# ham_ii_digital_interface.net
KiCad netlist of a schematic drawn in EAGLE
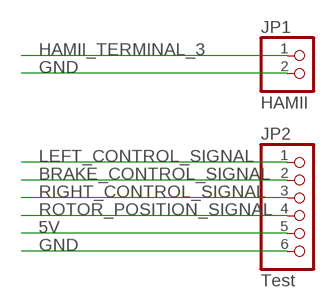
[diagram p0: schematic, sheet 1]
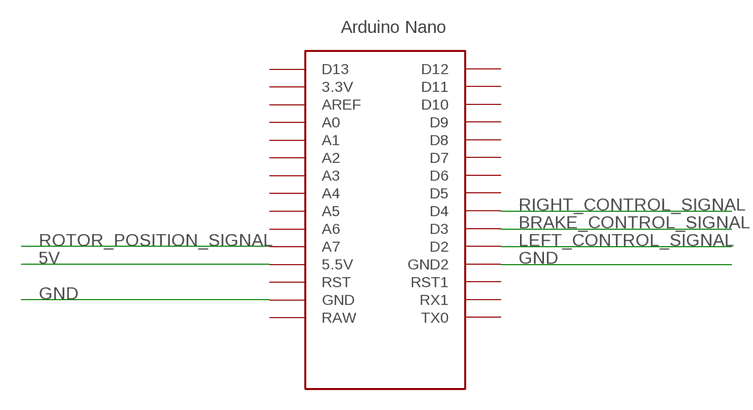
[diagram p1: schematic, sheet 2]
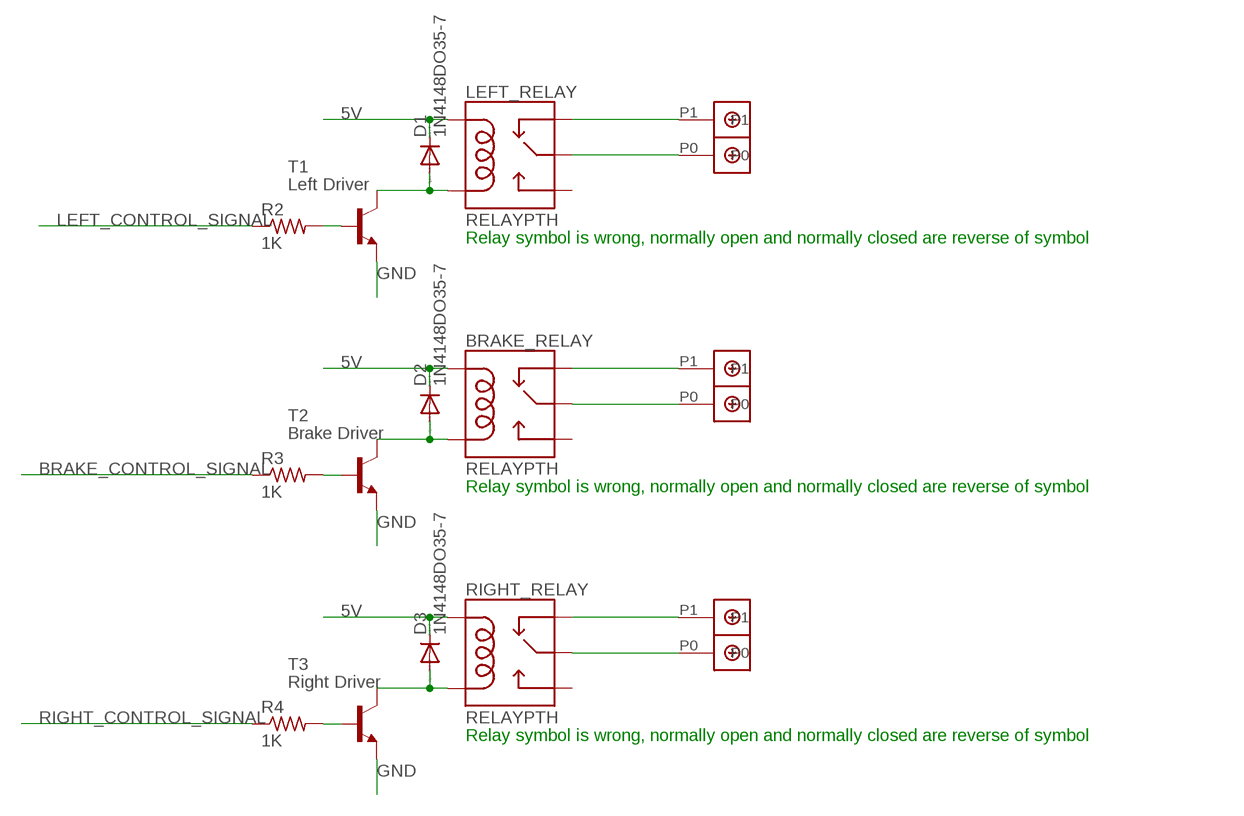
[diagram p2: schematic, sheet 3]
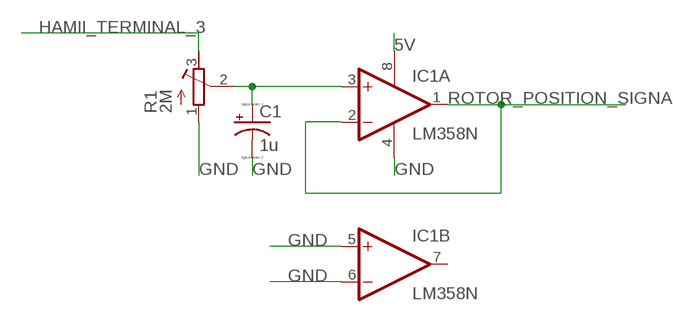
[diagram p3: schematic, sheet 4]

(export (version "E")
  (design (tool "Eeschema 10.0.6"))
  (components
    (comp (ref "C1")
      (value "1u")
      (footprint "eagle-import:E2-5")
      (libsource (lib "eagle-import") (part "CPOL-USE2-5"))
    )
    (comp (ref "IC1")
      (value "LM358N")
      (footprint "eagle-import:DIL08")
      (libsource (lib "eagle-import") (part "LM358N"))
    )
    (comp (ref "R1")
      (value "2M")
      (footprint "eagle-import:RTRIM3296W")
      (libsource (lib "eagle-import") (part "R-TRIMM3296W"))
    )
    (comp (ref "JP1")
      (value "HAMII")
      (footprint "eagle-import:1X02")
      (libsource (lib "eagle-import") (part "PINHD-1X2"))
    )
    (comp (ref "JP2")
      (value "Test")
      (footprint "eagle-import:1X06")
      (libsource (lib "eagle-import") (part "PINHD-1X6"))
    )
    (comp (ref "BRAKE_RELAY")
      (value "RELAYPTH")
      (footprint "eagle-import:SRD-05VDC-SL-C")
      (libsource (lib "eagle-import") (part "RELAYPTH"))
    )
    (comp (ref "D1")
      (value "1N4148DO35-7")
      (footprint "eagle-import:DO35-7")
      (libsource (lib "eagle-import") (part "1N4148DO35-7"))
    )
    (comp (ref "D2")
      (value "1N4148DO35-7")
      (footprint "eagle-import:DO35-7")
      (libsource (lib "eagle-import") (part "1N4148DO35-7"))
    )
    (comp (ref "D3")
      (value "1N4148DO35-7")
      (footprint "eagle-import:DO35-7")
      (libsource (lib "eagle-import") (part "1N4148DO35-7"))
    )
    (comp (ref "LEFT_RELAY")
      (value "RELAYPTH")
      (footprint "eagle-import:SRD-05VDC-SL-C")
      (libsource (lib "eagle-import") (part "RELAYPTH"))
    )
    (comp (ref "R2")
      (value "1K")
      (footprint "eagle-import:0207_10")
      (libsource (lib "eagle-import") (part "R-US_0207/10"))
    )
    (comp (ref "R3")
      (value "1K")
      (footprint "eagle-import:0207_10")
      (libsource (lib "eagle-import") (part "R-US_0207/10"))
    )
    (comp (ref "R4")
      (value "1K")
      (footprint "eagle-import:0207_10")
      (libsource (lib "eagle-import") (part "R-US_0207/10"))
    )
    (comp (ref "RIGHT_RELAY")
      (value "RELAYPTH")
      (footprint "eagle-import:SRD-05VDC-SL-C")
      (libsource (lib "eagle-import") (part "RELAYPTH"))
    )
    (comp (ref "T1")
      (value "Left Driver")
      (footprint "eagle-import:TO92")
      (libsource (lib "eagle-import") (part "-NPN-TO92"))
    )
    (comp (ref "T2")
      (value "Brake Driver")
      (footprint "eagle-import:TO92")
      (libsource (lib "eagle-import") (part "-NPN-TO92"))
    )
    (comp (ref "T3")
      (value "Right Driver")
      (footprint "eagle-import:TO92")
      (libsource (lib "eagle-import") (part "-NPN-TO92"))
    )
    (comp (ref "U$5")
      (value "DBCONN-1X2")
      (footprint "eagle-import:DBCONN-1X2")
      (libsource (lib "eagle-import") (part "DBCONN-1X2"))
    )
    (comp (ref "U$6")
      (value "DBCONN-1X2")
      (footprint "eagle-import:DBCONN-1X2")
      (libsource (lib "eagle-import") (part "DBCONN-1X2"))
    )
    (comp (ref "U$7")
      (value "DBCONN-1X2")
      (footprint "eagle-import:DBCONN-1X2")
      (libsource (lib "eagle-import") (part "DBCONN-1X2"))
    )
    (comp (ref "U$1")
      (value "NANO")
      (footprint "eagle-import:NANO")
      (libsource (lib "eagle-import") (part "NANO"))
    )
  )
  (nets
    (net (code "1") (name "5V") (class "Default")
      (node (ref "BRAKE_RELAY") (pin "COIL1") (pinfunction "COIL1_COIL1") (pintype "bidirectional"))
      (node (ref "D1") (pin "C") (pinfunction "C_C") (pintype "passive"))
      (node (ref "D2") (pin "C") (pinfunction "C_C") (pintype "passive"))
      (node (ref "D3") (pin "C") (pinfunction "C_C") (pintype "passive"))
      (node (ref "IC1") (pin "8") (pinfunction "V+_8") (pintype "power_in"))
      (node (ref "JP2") (pin "5") (pinfunction "5_5") (pintype "passive"))
      (node (ref "LEFT_RELAY") (pin "COIL1") (pinfunction "COIL1_COIL1") (pintype "bidirectional"))
      (node (ref "RIGHT_RELAY") (pin "COIL1") (pinfunction "COIL1_COIL1") (pintype "bidirectional"))
      (node (ref "U$1") (pin "5V") (pinfunction "5.5V_5V") (pintype "bidirectional"))
    )
    (net (code "2") (name "BRAKE_CONTROL_SIGNAL") (class "Default")
      (node (ref "JP2") (pin "2") (pinfunction "2_2") (pintype "passive"))
      (node (ref "R3") (pin "1") (pinfunction "1_1") (pintype "passive"))
      (node (ref "U$1") (pin "D3") (pinfunction "D3_D3") (pintype "bidirectional"))
    )
    (net (code "3") (name "GND") (class "Default")
      (node (ref "C1") (pin "-") (pinfunction "-_-") (pintype "passive"))
      (node (ref "IC1") (pin "4") (pinfunction "V-_4") (pintype "power_in"))
      (node (ref "IC1") (pin "5") (pinfunction "+IN_5") (pintype "input"))
      (node (ref "IC1") (pin "6") (pinfunction "-IN_6") (pintype "input"))
      (node (ref "JP1") (pin "2") (pinfunction "2_2") (pintype "passive"))
      (node (ref "JP2") (pin "6") (pinfunction "6_6") (pintype "passive"))
      (node (ref "R1") (pin "1") (pinfunction "A_1") (pintype "passive"))
      (node (ref "T1") (pin "1") (pinfunction "E_1") (pintype "passive"))
      (node (ref "T2") (pin "1") (pinfunction "E_1") (pintype "passive"))
      (node (ref "T3") (pin "1") (pinfunction "E_1") (pintype "passive"))
      (node (ref "U$1") (pin "GND") (pinfunction "GND_GND") (pintype "bidirectional"))
      (node (ref "U$1") (pin "GND1") (pinfunction "GND2_GND1") (pintype "bidirectional"))
    )
    (net (code "4") (name "HAMII_TERMINAL_3") (class "Default")
      (node (ref "JP1") (pin "1") (pinfunction "1_1") (pintype "passive"))
      (node (ref "R1") (pin "3") (pinfunction "E_3") (pintype "passive"))
    )
    (net (code "5") (name "LEFT_CONTROL_SIGNAL") (class "Default")
      (node (ref "JP2") (pin "1") (pinfunction "1_1") (pintype "passive"))
      (node (ref "R2") (pin "1") (pinfunction "1_1") (pintype "passive"))
      (node (ref "U$1") (pin "D2") (pinfunction "D2_D2") (pintype "bidirectional"))
    )
    (net (code "6") (name "Net-(BRAKE_RELAY-PadSWCOMMON)") (class "Default")
      (node (ref "BRAKE_RELAY") (pin "SWCOMMON") (pinfunction "SWCOMMON_SWCOMMON") (pintype "bidirectional"))
      (node (ref "U$6") (pin "P0") (pinfunction "P0_P0") (pintype "bidirectional"))
    )
    (net (code "7") (name "Net-(BRAKE_RELAY-SWCLOSE)") (class "Default")
      (node (ref "BRAKE_RELAY") (pin "SWCLOSED") (pinfunction "SWCLOSE_SWCLOSED") (pintype "bidirectional"))
      (node (ref "U$6") (pin "P1") (pinfunction "P1_P1") (pintype "bidirectional"))
    )
    (net (code "8") (name "Net-(IC1A-+IN)") (class "Default")
      (node (ref "C1") (pin "+") (pinfunction "+_+") (pintype "passive"))
      (node (ref "IC1") (pin "3") (pinfunction "+IN_3") (pintype "input"))
      (node (ref "R1") (pin "2") (pinfunction "S_2") (pintype "passive"))
    )
    (net (code "9") (name "Net-(LEFT_RELAY-PadSWCOMMON)") (class "Default")
      (node (ref "LEFT_RELAY") (pin "SWCOMMON") (pinfunction "SWCOMMON_SWCOMMON") (pintype "bidirectional"))
      (node (ref "U$5") (pin "P0") (pinfunction "P0_P0") (pintype "bidirectional"))
    )
    (net (code "10") (name "Net-(LEFT_RELAY-SWCLOSE)") (class "Default")
      (node (ref "LEFT_RELAY") (pin "SWCLOSED") (pinfunction "SWCLOSE_SWCLOSED") (pintype "bidirectional"))
      (node (ref "U$5") (pin "P1") (pinfunction "P1_P1") (pintype "bidirectional"))
    )
    (net (code "11") (name "Net-(RIGHT_RELAY-PadSWCOMMON)") (class "Default")
      (node (ref "RIGHT_RELAY") (pin "SWCOMMON") (pinfunction "SWCOMMON_SWCOMMON") (pintype "bidirectional"))
      (node (ref "U$7") (pin "P0") (pinfunction "P0_P0") (pintype "bidirectional"))
    )
    (net (code "12") (name "Net-(RIGHT_RELAY-SWCLOSE)") (class "Default")
      (node (ref "RIGHT_RELAY") (pin "SWCLOSED") (pinfunction "SWCLOSE_SWCLOSED") (pintype "bidirectional"))
      (node (ref "U$7") (pin "P1") (pinfunction "P1_P1") (pintype "bidirectional"))
    )
    (net (code "13") (name "Net-(T1-B)") (class "Default")
      (node (ref "R2") (pin "2") (pinfunction "2_2") (pintype "passive"))
      (node (ref "T1") (pin "2") (pinfunction "B_2") (pintype "passive"))
    )
    (net (code "14") (name "Net-(T1-C)") (class "Default")
      (node (ref "D1") (pin "A") (pinfunction "A_A") (pintype "passive"))
      (node (ref "LEFT_RELAY") (pin "COIL0") (pinfunction "COIL0_COIL0") (pintype "bidirectional"))
      (node (ref "T1") (pin "3") (pinfunction "C_3") (pintype "passive"))
    )
    (net (code "15") (name "Net-(T2-B)") (class "Default")
      (node (ref "R3") (pin "2") (pinfunction "2_2") (pintype "passive"))
      (node (ref "T2") (pin "2") (pinfunction "B_2") (pintype "passive"))
    )
    (net (code "16") (name "Net-(T2-C)") (class "Default")
      (node (ref "BRAKE_RELAY") (pin "COIL0") (pinfunction "COIL0_COIL0") (pintype "bidirectional"))
      (node (ref "D2") (pin "A") (pinfunction "A_A") (pintype "passive"))
      (node (ref "T2") (pin "3") (pinfunction "C_3") (pintype "passive"))
    )
    (net (code "17") (name "Net-(T3-B)") (class "Default")
      (node (ref "R4") (pin "2") (pinfunction "2_2") (pintype "passive"))
      (node (ref "T3") (pin "2") (pinfunction "B_2") (pintype "passive"))
    )
    (net (code "18") (name "Net-(T3-C)") (class "Default")
      (node (ref "D3") (pin "A") (pinfunction "A_A") (pintype "passive"))
      (node (ref "RIGHT_RELAY") (pin "COIL0") (pinfunction "COIL0_COIL0") (pintype "bidirectional"))
      (node (ref "T3") (pin "3") (pinfunction "C_3") (pintype "passive"))
    )
    (net (code "19") (name "RIGHT_CONTROL_SIGNAL") (class "Default")
      (node (ref "JP2") (pin "3") (pinfunction "3_3") (pintype "passive"))
      (node (ref "R4") (pin "1") (pinfunction "1_1") (pintype "passive"))
      (node (ref "U$1") (pin "D4") (pinfunction "D4_D4") (pintype "bidirectional"))
    )
    (net (code "20") (name "ROTOR_POSITION_SIGNAL") (class "Default")
      (node (ref "IC1") (pin "1") (pinfunction "OUT_1") (pintype "output"))
      (node (ref "IC1") (pin "2") (pinfunction "-IN_2") (pintype "input"))
      (node (ref "JP2") (pin "4") (pinfunction "4_4") (pintype "passive"))
      (node (ref "U$1") (pin "A7") (pinfunction "A7_A7") (pintype "bidirectional"))
    )
    (net (code "21") (name "unconnected-(BRAKE_RELAY-PadSWOPEN)") (class "Default")
      (node (ref "BRAKE_RELAY") (pin "SWOPEN") (pinfunction "SWOPEN_SWOPEN") (pintype "bidirectional"))
    )
    (net (code "22") (name "unconnected-(IC1B-OUT-Pad7)") (class "Default")
      (node (ref "IC1") (pin "7") (pinfunction "OUT_7") (pintype "output"))
    )
    (net (code "23") (name "unconnected-(LEFT_RELAY-PadSWOPEN)") (class "Default")
      (node (ref "LEFT_RELAY") (pin "SWOPEN") (pinfunction "SWOPEN_SWOPEN") (pintype "bidirectional"))
    )
    (net (code "24") (name "unconnected-(RIGHT_RELAY-PadSWOPEN)") (class "Default")
      (node (ref "RIGHT_RELAY") (pin "SWOPEN") (pinfunction "SWOPEN_SWOPEN") (pintype "bidirectional"))
    )
    (net (code "25") (name "unconnected-(U$1-Pad3.3V)") (class "Default")
      (node (ref "U$1") (pin "3.3V") (pinfunction "3.3V_3.3V") (pintype "bidirectional"))
    )
    (net (code "26") (name "unconnected-(U$1-PadA0)") (class "Default")
      (node (ref "U$1") (pin "A0") (pinfunction "A0_A0") (pintype "bidirectional"))
    )
    (net (code "27") (name "unconnected-(U$1-PadA1)") (class "Default")
      (node (ref "U$1") (pin "A1") (pinfunction "A1_A1") (pintype "bidirectional"))
    )
    (net (code "28") (name "unconnected-(U$1-PadA2)") (class "Default")
      (node (ref "U$1") (pin "A2") (pinfunction "A2_A2") (pintype "bidirectional"))
    )
    (net (code "29") (name "unconnected-(U$1-PadA3)") (class "Default")
      (node (ref "U$1") (pin "A3") (pinfunction "A3_A3") (pintype "bidirectional"))
    )
    (net (code "30") (name "unconnected-(U$1-PadA4)") (class "Default")
      (node (ref "U$1") (pin "A4") (pinfunction "A4_A4") (pintype "bidirectional"))
    )
    (net (code "31") (name "unconnected-(U$1-PadA5)") (class "Default")
      (node (ref "U$1") (pin "A5") (pinfunction "A5_A5") (pintype "bidirectional"))
    )
    (net (code "32") (name "unconnected-(U$1-PadA6)") (class "Default")
      (node (ref "U$1") (pin "A6") (pinfunction "A6_A6") (pintype "bidirectional"))
    )
    (net (code "33") (name "unconnected-(U$1-PadAREF)") (class "Default")
      (node (ref "U$1") (pin "AREF") (pinfunction "AREF_AREF") (pintype "bidirectional"))
    )
    (net (code "34") (name "unconnected-(U$1-PadD5)") (class "Default")
      (node (ref "U$1") (pin "D5") (pinfunction "D5_D5") (pintype "bidirectional"))
    )
    (net (code "35") (name "unconnected-(U$1-PadD6)") (class "Default")
      (node (ref "U$1") (pin "D6") (pinfunction "D6_D6") (pintype "bidirectional"))
    )
    (net (code "36") (name "unconnected-(U$1-PadD7)") (class "Default")
      (node (ref "U$1") (pin "D7") (pinfunction "D7_D7") (pintype "bidirectional"))
    )
    (net (code "37") (name "unconnected-(U$1-PadD8)") (class "Default")
      (node (ref "U$1") (pin "D8") (pinfunction "D8_D8") (pintype "bidirectional"))
    )
    (net (code "38") (name "unconnected-(U$1-PadD9)") (class "Default")
      (node (ref "U$1") (pin "D9") (pinfunction "D9_D9") (pintype "bidirectional"))
    )
    (net (code "39") (name "unconnected-(U$1-PadD10)") (class "Default")
      (node (ref "U$1") (pin "D10") (pinfunction "D10_D10") (pintype "bidirectional"))
    )
    (net (code "40") (name "unconnected-(U$1-PadD11)") (class "Default")
      (node (ref "U$1") (pin "D11") (pinfunction "D11_D11") (pintype "bidirectional"))
    )
    (net (code "41") (name "unconnected-(U$1-PadD12)") (class "Default")
      (node (ref "U$1") (pin "D12") (pinfunction "D12_D12") (pintype "bidirectional"))
    )
    (net (code "42") (name "unconnected-(U$1-PadD13)") (class "Default")
      (node (ref "U$1") (pin "D13") (pinfunction "D13_D13") (pintype "bidirectional"))
    )
    (net (code "43") (name "unconnected-(U$1-PadICSP1)") (class "Default")
      (node (ref "U$1") (pin "ICSP1") (pinfunction "ICSP1_ICSP1") (pintype "bidirectional"))
    )
    (net (code "44") (name "unconnected-(U$1-PadICSP2)") (class "Default")
      (node (ref "U$1") (pin "ICSP2") (pinfunction "ICSP2_ICSP2") (pintype "bidirectional"))
    )
    (net (code "45") (name "unconnected-(U$1-PadICSP3)") (class "Default")
      (node (ref "U$1") (pin "ICSP3") (pinfunction "ICSP3_ICSP3") (pintype "bidirectional"))
    )
    (net (code "46") (name "unconnected-(U$1-PadICSP4)") (class "Default")
      (node (ref "U$1") (pin "ICSP4") (pinfunction "ICSP4_ICSP4") (pintype "bidirectional"))
    )
    (net (code "47") (name "unconnected-(U$1-PadICSP5)") (class "Default")
      (node (ref "U$1") (pin "ICSP5") (pinfunction "ICSP5_ICSP5") (pintype "bidirectional"))
    )
    (net (code "48") (name "unconnected-(U$1-PadICSP6)") (class "Default")
      (node (ref "U$1") (pin "ICSP6") (pinfunction "ICSP6_ICSP6") (pintype "bidirectional"))
    )
    (net (code "49") (name "unconnected-(U$1-PadRAW)") (class "Default")
      (node (ref "U$1") (pin "RAW") (pinfunction "RAW_RAW") (pintype "bidirectional"))
    )
    (net (code "50") (name "unconnected-(U$1-PadRST)") (class "Default")
      (node (ref "U$1") (pin "RST") (pinfunction "RST_RST") (pintype "bidirectional"))
    )
    (net (code "51") (name "unconnected-(U$1-PadRST1)") (class "Default")
      (node (ref "U$1") (pin "RST1") (pinfunction "RST1_RST1") (pintype "bidirectional"))
    )
    (net (code "52") (name "unconnected-(U$1-PadRX1)") (class "Default")
      (node (ref "U$1") (pin "RX1") (pinfunction "RX1_RX1") (pintype "bidirectional"))
    )
    (net (code "53") (name "unconnected-(U$1-PadTX0)") (class "Default")
      (node (ref "U$1") (pin "TX0") (pinfunction "TX0_TX0") (pintype "bidirectional"))
    )
  )
)
